# Sheet1.net
KiCad netlist of a schematic drawn in Altium Designer
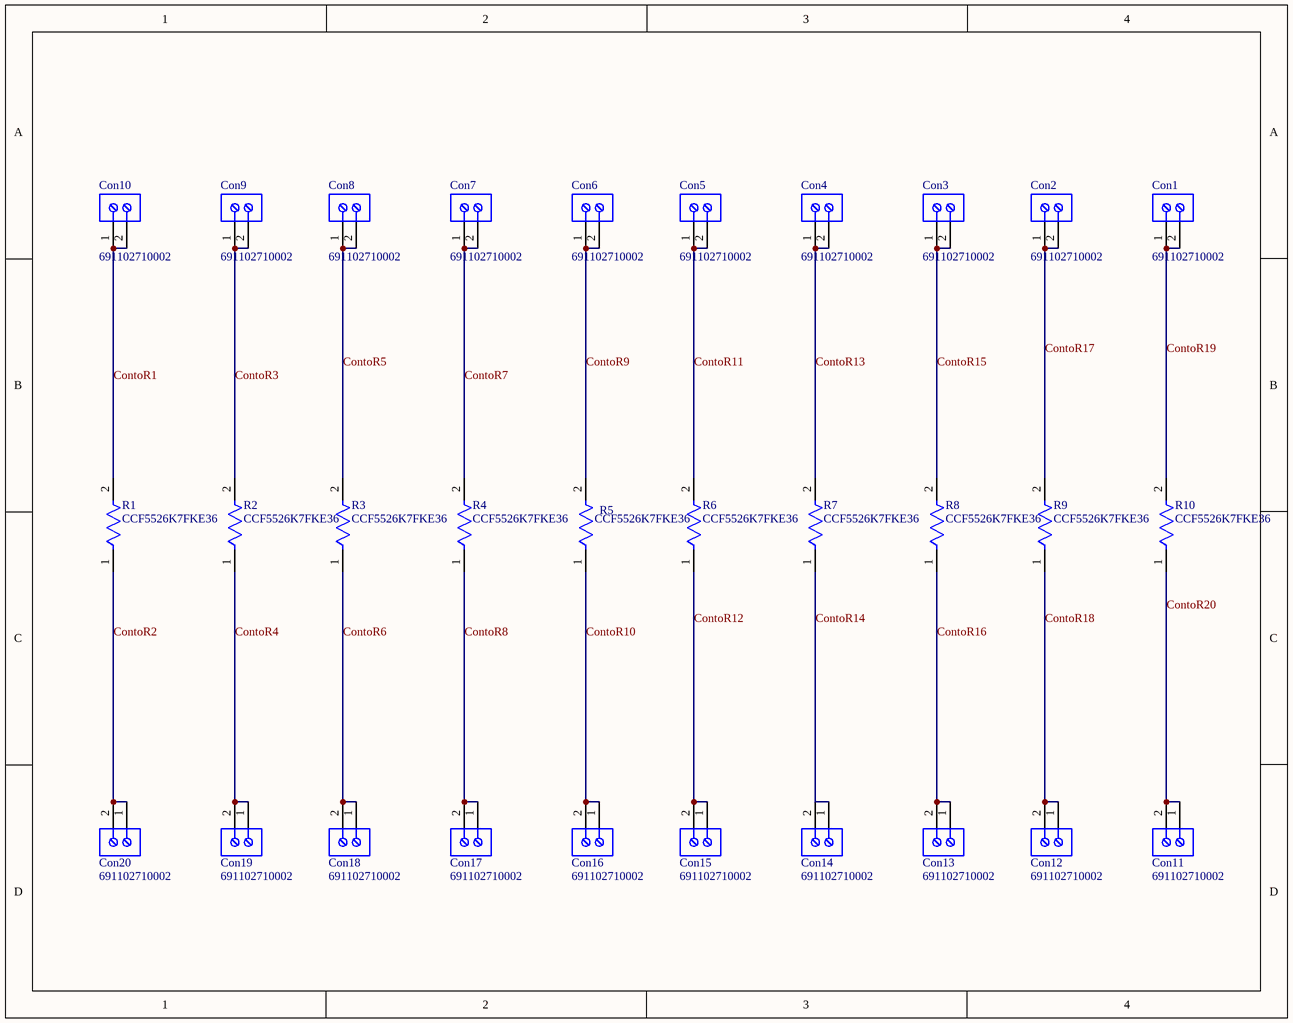
[diagram p0: Sheet1.SchDoc]

(export (version "E")
  (design (tool "Eeschema 10.0.6"))
  (components
    (comp (ref "Con1")
      (value "691102710002")
      (footprint "691102710002")
      (fields (field (name "VOLTAGE") "300V"))
      (libsource (lib "Altium Content Vault") (part "TBL - 1R - 02P - Screw"))
    )
    (comp (ref "Con2")
      (value "691102710002")
      (footprint "691102710002")
      (fields (field (name "VOLTAGE") "300V"))
      (libsource (lib "Altium Content Vault") (part "TBL - 1R - 02P - Screw"))
    )
    (comp (ref "Con3")
      (value "691102710002")
      (footprint "691102710002")
      (fields (field (name "VOLTAGE") "300V"))
      (libsource (lib "Altium Content Vault") (part "TBL - 1R - 02P - Screw"))
    )
    (comp (ref "Con4")
      (value "691102710002")
      (footprint "691102710002")
      (fields (field (name "VOLTAGE") "300V"))
      (libsource (lib "Altium Content Vault") (part "TBL - 1R - 02P - Screw"))
    )
    (comp (ref "Con5")
      (value "691102710002")
      (footprint "691102710002")
      (fields (field (name "VOLTAGE") "300V"))
      (libsource (lib "Altium Content Vault") (part "TBL - 1R - 02P - Screw"))
    )
    (comp (ref "Con6")
      (value "691102710002")
      (footprint "691102710002")
      (fields (field (name "VOLTAGE") "300V"))
      (libsource (lib "Altium Content Vault") (part "TBL - 1R - 02P - Screw"))
    )
    (comp (ref "Con7")
      (value "691102710002")
      (footprint "691102710002")
      (fields (field (name "VOLTAGE") "300V"))
      (libsource (lib "Altium Content Vault") (part "TBL - 1R - 02P - Screw"))
    )
    (comp (ref "Con8")
      (value "691102710002")
      (footprint "691102710002")
      (fields (field (name "VOLTAGE") "300V"))
      (libsource (lib "Altium Content Vault") (part "TBL - 1R - 02P - Screw"))
    )
    (comp (ref "Con9")
      (value "691102710002")
      (footprint "691102710002")
      (fields (field (name "VOLTAGE") "300V"))
      (libsource (lib "Altium Content Vault") (part "TBL - 1R - 02P - Screw"))
    )
    (comp (ref "Con10")
      (value "691102710002")
      (footprint "691102710002")
      (fields (field (name "VOLTAGE") "300V"))
      (libsource (lib "Altium Content Vault") (part "TBL - 1R - 02P - Screw"))
    )
    (comp (ref "Con11")
      (value "691102710002")
      (footprint "691102710002")
      (fields (field (name "VOLTAGE") "300V"))
      (libsource (lib "Altium Content Vault") (part "TBL - 1R - 02P - Screw"))
    )
    (comp (ref "Con12")
      (value "691102710002")
      (footprint "691102710002")
      (fields (field (name "VOLTAGE") "300V"))
      (libsource (lib "Altium Content Vault") (part "TBL - 1R - 02P - Screw"))
    )
    (comp (ref "Con13")
      (value "691102710002")
      (footprint "691102710002")
      (fields (field (name "VOLTAGE") "300V"))
      (libsource (lib "Altium Content Vault") (part "TBL - 1R - 02P - Screw"))
    )
    (comp (ref "Con14")
      (value "691102710002")
      (footprint "691102710002")
      (fields (field (name "VOLTAGE") "300V"))
      (libsource (lib "Altium Content Vault") (part "TBL - 1R - 02P - Screw"))
    )
    (comp (ref "Con15")
      (value "691102710002")
      (footprint "691102710002")
      (fields (field (name "VOLTAGE") "300V"))
      (libsource (lib "Altium Content Vault") (part "TBL - 1R - 02P - Screw"))
    )
    (comp (ref "Con16")
      (value "691102710002")
      (footprint "691102710002")
      (fields (field (name "VOLTAGE") "300V"))
      (libsource (lib "Altium Content Vault") (part "TBL - 1R - 02P - Screw"))
    )
    (comp (ref "Con17")
      (value "691102710002")
      (footprint "691102710002")
      (fields (field (name "VOLTAGE") "300V"))
      (libsource (lib "Altium Content Vault") (part "TBL - 1R - 02P - Screw"))
    )
    (comp (ref "Con18")
      (value "691102710002")
      (footprint "691102710002")
      (fields (field (name "VOLTAGE") "300V"))
      (libsource (lib "Altium Content Vault") (part "TBL - 1R - 02P - Screw"))
    )
    (comp (ref "Con19")
      (value "691102710002")
      (footprint "691102710002")
      (fields (field (name "VOLTAGE") "300V"))
      (libsource (lib "Altium Content Vault") (part "TBL - 1R - 02P - Screw"))
    )
    (comp (ref "Con20")
      (value "691102710002")
      (footprint "691102710002")
      (fields (field (name "VOLTAGE") "300V"))
      (libsource (lib "Altium Content Vault") (part "TBL - 1R - 02P - Screw"))
    )
    (comp (ref "R1")
      (value "CCF5526K7FKE36")
      (footprint "FP-CCF55-MFG")
      (description "CCF5526K7FKE36 Res Metal Film 26.7K Ohm 1% 1/4W 1/2W ±100ppm/°C Conformal AXL Thru-Hole T/R")
      (fields (field (name "TOLERANCE") "1%"))
      (libsource (lib "Altium Content Vault") (part "1029c3af85768c4190bb7ad29bc67b5"))
    )
    (comp (ref "R2")
      (value "CCF5526K7FKE36")
      (footprint "FP-CCF55-MFG")
      (description "CCF5526K7FKE36 Res Metal Film 26.7K Ohm 1% 1/4W 1/2W ±100ppm/°C Conformal AXL Thru-Hole T/R")
      (fields (field (name "TOLERANCE") "1%"))
      (libsource (lib "Altium Content Vault") (part "1029c3af85768c4190bb7ad29bc67b5"))
    )
    (comp (ref "R3")
      (value "CCF5526K7FKE36")
      (footprint "FP-CCF55-MFG")
      (description "CCF5526K7FKE36 Res Metal Film 26.7K Ohm 1% 1/4W 1/2W ±100ppm/°C Conformal AXL Thru-Hole T/R")
      (fields (field (name "TOLERANCE") "1%"))
      (libsource (lib "Altium Content Vault") (part "1029c3af85768c4190bb7ad29bc67b5"))
    )
    (comp (ref "R4")
      (value "CCF5526K7FKE36")
      (footprint "FP-CCF55-MFG")
      (description "CCF5526K7FKE36 Res Metal Film 26.7K Ohm 1% 1/4W 1/2W ±100ppm/°C Conformal AXL Thru-Hole T/R")
      (fields (field (name "TOLERANCE") "1%"))
      (libsource (lib "Altium Content Vault") (part "1029c3af85768c4190bb7ad29bc67b5"))
    )
    (comp (ref "R5")
      (value "CCF5526K7FKE36")
      (footprint "FP-CCF55-MFG")
      (description "CCF5526K7FKE36 Res Metal Film 26.7K Ohm 1% 1/4W 1/2W ±100ppm/°C Conformal AXL Thru-Hole T/R")
      (fields (field (name "TOLERANCE") "1%"))
      (libsource (lib "Altium Content Vault") (part "1029c3af85768c4190bb7ad29bc67b5"))
    )
    (comp (ref "R6")
      (value "CCF5526K7FKE36")
      (footprint "FP-CCF55-MFG")
      (description "CCF5526K7FKE36 Res Metal Film 26.7K Ohm 1% 1/4W 1/2W ±100ppm/°C Conformal AXL Thru-Hole T/R")
      (fields (field (name "TOLERANCE") "1%"))
      (libsource (lib "Altium Content Vault") (part "1029c3af85768c4190bb7ad29bc67b5"))
    )
    (comp (ref "R7")
      (value "CCF5526K7FKE36")
      (footprint "FP-CCF55-MFG")
      (description "CCF5526K7FKE36 Res Metal Film 26.7K Ohm 1% 1/4W 1/2W ±100ppm/°C Conformal AXL Thru-Hole T/R")
      (fields (field (name "TOLERANCE") "1%"))
      (libsource (lib "Altium Content Vault") (part "1029c3af85768c4190bb7ad29bc67b5"))
    )
    (comp (ref "R8")
      (value "CCF5526K7FKE36")
      (footprint "FP-CCF55-MFG")
      (description "CCF5526K7FKE36 Res Metal Film 26.7K Ohm 1% 1/4W 1/2W ±100ppm/°C Conformal AXL Thru-Hole T/R")
      (fields (field (name "TOLERANCE") "1%"))
      (libsource (lib "Altium Content Vault") (part "1029c3af85768c4190bb7ad29bc67b5"))
    )
    (comp (ref "R9")
      (value "CCF5526K7FKE36")
      (footprint "FP-CCF55-MFG")
      (description "CCF5526K7FKE36 Res Metal Film 26.7K Ohm 1% 1/4W 1/2W ±100ppm/°C Conformal AXL Thru-Hole T/R")
      (fields (field (name "TOLERANCE") "1%"))
      (libsource (lib "Altium Content Vault") (part "1029c3af85768c4190bb7ad29bc67b5"))
    )
    (comp (ref "R10")
      (value "CCF5526K7FKE36")
      (footprint "FP-CCF55-MFG")
      (description "CCF5526K7FKE36 Res Metal Film 26.7K Ohm 1% 1/4W 1/2W ±100ppm/°C Conformal AXL Thru-Hole T/R")
      (fields (field (name "TOLERANCE") "1%"))
      (libsource (lib "Altium Content Vault") (part "1029c3af85768c4190bb7ad29bc67b5"))
    )
  )
  (nets
    (net (code "1") (name "/ContoR1") (class "Default")
      (node (ref "Con10") (pin "1") (pinfunction "1_1") (pintype "passive"))
      (node (ref "Con10") (pin "2") (pinfunction "2_2") (pintype "passive"))
      (node (ref "R1") (pin "2") (pinfunction "2_2") (pintype "passive"))
    )
    (net (code "2") (name "/ContoR2") (class "Default")
      (node (ref "Con20") (pin "1") (pinfunction "1_1") (pintype "passive"))
      (node (ref "Con20") (pin "2") (pinfunction "2_2") (pintype "passive"))
      (node (ref "R1") (pin "1") (pinfunction "1_1") (pintype "passive"))
    )
    (net (code "3") (name "/ContoR3") (class "Default")
      (node (ref "Con9") (pin "1") (pinfunction "1_1") (pintype "passive"))
      (node (ref "Con9") (pin "2") (pinfunction "2_2") (pintype "passive"))
      (node (ref "R2") (pin "2") (pinfunction "2_2") (pintype "passive"))
    )
    (net (code "4") (name "/ContoR4") (class "Default")
      (node (ref "Con19") (pin "1") (pinfunction "1_1") (pintype "passive"))
      (node (ref "Con19") (pin "2") (pinfunction "2_2") (pintype "passive"))
      (node (ref "R2") (pin "1") (pinfunction "1_1") (pintype "passive"))
    )
    (net (code "5") (name "/ContoR5") (class "Default")
      (node (ref "Con8") (pin "1") (pinfunction "1_1") (pintype "passive"))
      (node (ref "Con8") (pin "2") (pinfunction "2_2") (pintype "passive"))
      (node (ref "R3") (pin "2") (pinfunction "2_2") (pintype "passive"))
    )
    (net (code "6") (name "/ContoR6") (class "Default")
      (node (ref "Con18") (pin "1") (pinfunction "1_1") (pintype "passive"))
      (node (ref "Con18") (pin "2") (pinfunction "2_2") (pintype "passive"))
      (node (ref "R3") (pin "1") (pinfunction "1_1") (pintype "passive"))
    )
    (net (code "7") (name "/ContoR7") (class "Default")
      (node (ref "Con7") (pin "1") (pinfunction "1_1") (pintype "passive"))
      (node (ref "Con7") (pin "2") (pinfunction "2_2") (pintype "passive"))
      (node (ref "R4") (pin "2") (pinfunction "2_2") (pintype "passive"))
    )
    (net (code "8") (name "/ContoR8") (class "Default")
      (node (ref "Con17") (pin "1") (pinfunction "1_1") (pintype "passive"))
      (node (ref "Con17") (pin "2") (pinfunction "2_2") (pintype "passive"))
      (node (ref "R4") (pin "1") (pinfunction "1_1") (pintype "passive"))
    )
    (net (code "9") (name "/ContoR9") (class "Default")
      (node (ref "Con6") (pin "1") (pinfunction "1_1") (pintype "passive"))
      (node (ref "Con6") (pin "2") (pinfunction "2_2") (pintype "passive"))
      (node (ref "R5") (pin "2") (pinfunction "2_2") (pintype "passive"))
    )
    (net (code "10") (name "/ContoR10") (class "Default")
      (node (ref "Con16") (pin "1") (pinfunction "1_1") (pintype "passive"))
      (node (ref "Con16") (pin "2") (pinfunction "2_2") (pintype "passive"))
      (node (ref "R5") (pin "1") (pinfunction "1_1") (pintype "passive"))
    )
    (net (code "11") (name "/ContoR11") (class "Default")
      (node (ref "Con5") (pin "1") (pinfunction "1_1") (pintype "passive"))
      (node (ref "Con5") (pin "2") (pinfunction "2_2") (pintype "passive"))
      (node (ref "R6") (pin "2") (pinfunction "2_2") (pintype "passive"))
    )
    (net (code "12") (name "/ContoR12") (class "Default")
      (node (ref "Con15") (pin "1") (pinfunction "1_1") (pintype "passive"))
      (node (ref "Con15") (pin "2") (pinfunction "2_2") (pintype "passive"))
      (node (ref "R6") (pin "1") (pinfunction "1_1") (pintype "passive"))
    )
    (net (code "13") (name "/ContoR13") (class "Default")
      (node (ref "Con4") (pin "1") (pinfunction "1_1") (pintype "passive"))
      (node (ref "Con4") (pin "2") (pinfunction "2_2") (pintype "passive"))
      (node (ref "R7") (pin "2") (pinfunction "2_2") (pintype "passive"))
    )
    (net (code "14") (name "/ContoR14") (class "Default")
      (node (ref "Con14") (pin "1") (pinfunction "1_1") (pintype "passive"))
      (node (ref "Con14") (pin "2") (pinfunction "2_2") (pintype "passive"))
      (node (ref "R7") (pin "1") (pinfunction "1_1") (pintype "passive"))
    )
    (net (code "15") (name "/ContoR15") (class "Default")
      (node (ref "Con3") (pin "1") (pinfunction "1_1") (pintype "passive"))
      (node (ref "Con3") (pin "2") (pinfunction "2_2") (pintype "passive"))
      (node (ref "R8") (pin "2") (pinfunction "2_2") (pintype "passive"))
    )
    (net (code "16") (name "/ContoR16") (class "Default")
      (node (ref "Con13") (pin "1") (pinfunction "1_1") (pintype "passive"))
      (node (ref "Con13") (pin "2") (pinfunction "2_2") (pintype "passive"))
      (node (ref "R8") (pin "1") (pinfunction "1_1") (pintype "passive"))
    )
    (net (code "17") (name "/ContoR17") (class "Default")
      (node (ref "Con2") (pin "1") (pinfunction "1_1") (pintype "passive"))
      (node (ref "Con2") (pin "2") (pinfunction "2_2") (pintype "passive"))
      (node (ref "R9") (pin "2") (pinfunction "2_2") (pintype "passive"))
    )
    (net (code "18") (name "/ContoR18") (class "Default")
      (node (ref "Con12") (pin "1") (pinfunction "1_1") (pintype "passive"))
      (node (ref "Con12") (pin "2") (pinfunction "2_2") (pintype "passive"))
      (node (ref "R9") (pin "1") (pinfunction "1_1") (pintype "passive"))
    )
    (net (code "19") (name "/ContoR19") (class "Default")
      (node (ref "Con1") (pin "1") (pinfunction "1_1") (pintype "passive"))
      (node (ref "Con1") (pin "2") (pinfunction "2_2") (pintype "passive"))
      (node (ref "R10") (pin "2") (pinfunction "2_2") (pintype "passive"))
    )
    (net (code "20") (name "/ContoR20") (class "Default")
      (node (ref "Con11") (pin "1") (pinfunction "1_1") (pintype "passive"))
      (node (ref "Con11") (pin "2") (pinfunction "2_2") (pintype "passive"))
      (node (ref "R10") (pin "1") (pinfunction "1_1") (pintype "passive"))
    )
  )
)
